# Candunio.net
KiCad netlist of a schematic drawn in Altium Designer
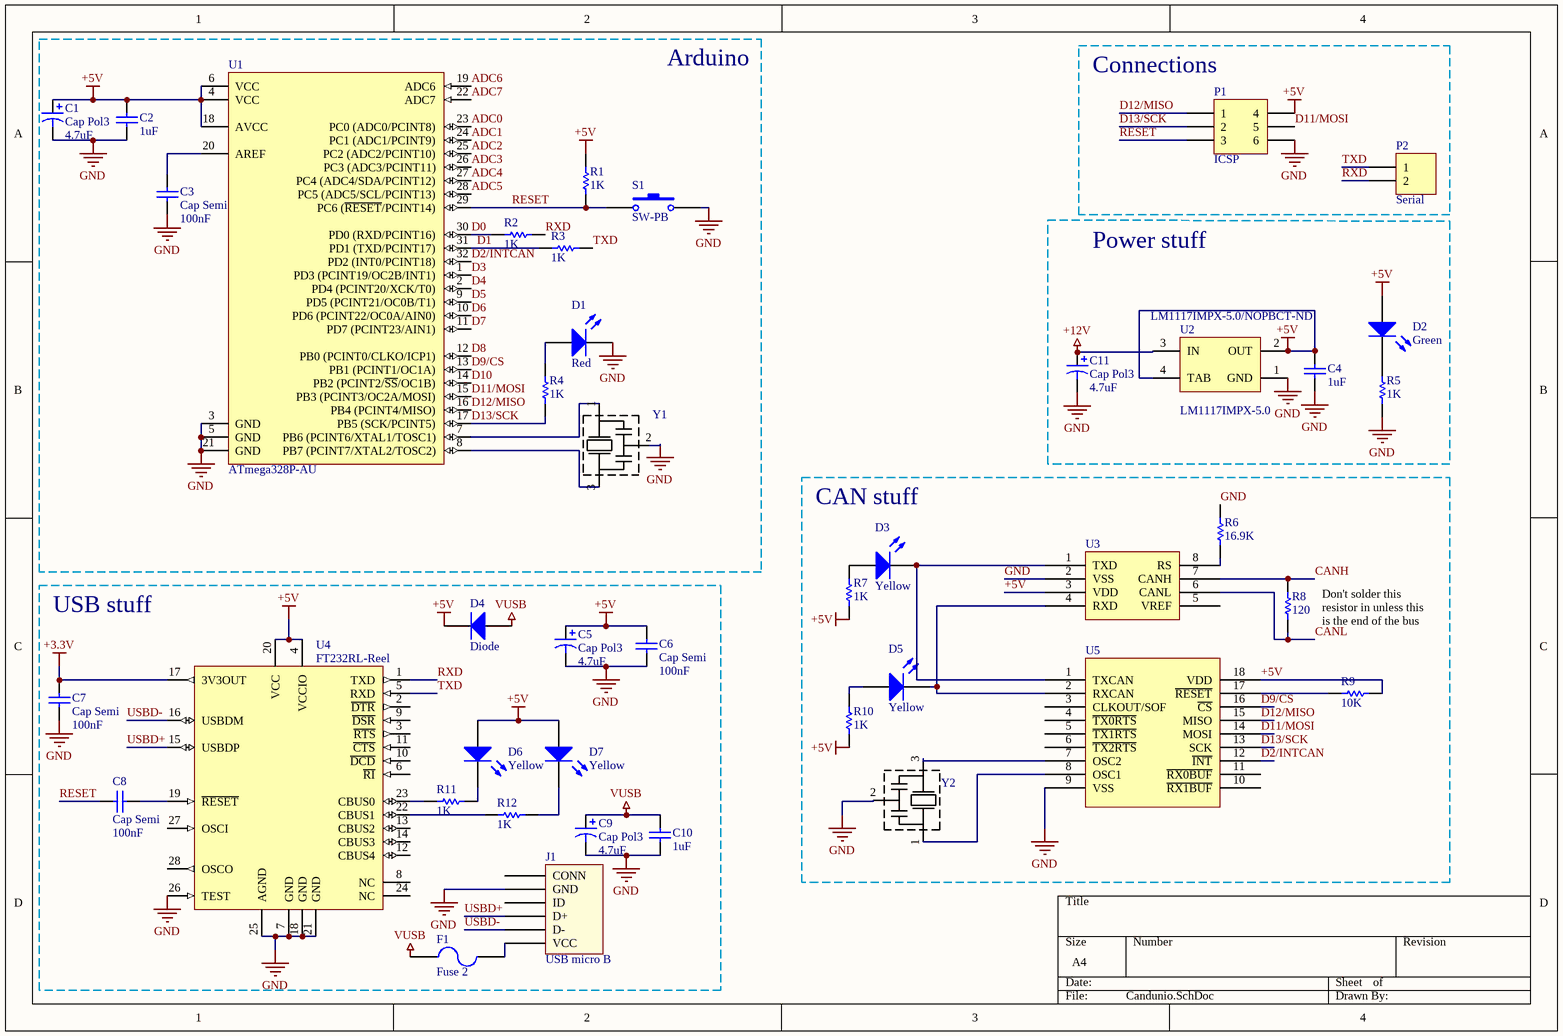
[diagram p0: Candunio.SchDoc]

(export (version "E")
  (design (tool "Eeschema 10.0.6"))
  (components
    (comp (ref "C1")
      (value "Cap Pol3")
      (footprint "C1206")
      (description "Polarized Capacitor (Surface Mount)")
      (fields
        (field (name "ALTIUM_VALUE") "4.7uF")
        (field (name "MANUFACTURER") "Kyocera AVX")
        (field (name "MANUFACTURER PART NUMBER") "12063C475KAT2A")
        (field (name "PUBLISHER") "Altium Limited")
      )
      (libsource (lib "Miscellaneous Devices") (part "Cap Pol3"))
    )
    (comp (ref "C2")
      (value "1uF")
      (footprint "C1206")
      (description "Capacitor (Semiconductor SIM Model)")
      (fields
        (field (name "MANUFACTURER") "Murata")
        (field (name "MANUFACTURER PART NUMBER") "GRM31MR71H105KA88L")
        (field (name "PUBLISHER") "Altium Limited")
      )
      (libsource (lib "Miscellaneous Devices") (part "Cap Semi"))
    )
    (comp (ref "C3")
      (value "Cap Semi")
      (footprint "C1206")
      (description "Capacitor (Semiconductor SIM Model)")
      (fields
        (field (name "ALTIUM_VALUE") "100nF")
        (field (name "MANUFACTURER") "Yageo")
        (field (name "MANUFACTURER PART NUMBER") "CC1206KKX7R0BB104")
        (field (name "PUBLISHER") "Altium Limited")
      )
      (libsource (lib "Miscellaneous Devices") (part "Cap Semi"))
    )
    (comp (ref "C4")
      (value "1uF")
      (footprint "C1206")
      (description "Capacitor (Semiconductor SIM Model)")
      (fields
        (field (name "MANUFACTURER") "Murata")
        (field (name "MANUFACTURER PART NUMBER") "GRM31MR71H105KA88L")
        (field (name "PUBLISHER") "Altium Limited")
      )
      (libsource (lib "Miscellaneous Devices") (part "Cap Semi"))
    )
    (comp (ref "C5")
      (value "Cap Pol3")
      (footprint "C1206")
      (description "Polarized Capacitor (Surface Mount)")
      (fields
        (field (name "ALTIUM_VALUE") "4.7uF")
        (field (name "MANUFACTURER") "Kyocera AVX")
        (field (name "MANUFACTURER PART NUMBER") "12063C475KAT2A")
        (field (name "PUBLISHER") "Altium Limited")
      )
      (libsource (lib "Miscellaneous Devices") (part "Cap Pol3"))
    )
    (comp (ref "C6")
      (value "Cap Semi")
      (footprint "C1206")
      (description "Capacitor (Semiconductor SIM Model)")
      (fields
        (field (name "ALTIUM_VALUE") "100nF")
        (field (name "MANUFACTURER") "Yageo")
        (field (name "MANUFACTURER PART NUMBER") "CC1206KKX7R0BB104")
        (field (name "PUBLISHER") "Altium Limited")
      )
      (libsource (lib "Miscellaneous Devices") (part "Cap Semi"))
    )
    (comp (ref "C7")
      (value "Cap Semi")
      (footprint "C1206")
      (description "Capacitor (Semiconductor SIM Model)")
      (fields
        (field (name "ALTIUM_VALUE") "100nF")
        (field (name "MANUFACTURER") "Yageo")
        (field (name "MANUFACTURER PART NUMBER") "CC1206KKX7R0BB104")
        (field (name "PUBLISHER") "Altium Limited")
      )
      (libsource (lib "Miscellaneous Devices") (part "Cap Semi"))
    )
    (comp (ref "C8")
      (value "Cap Semi")
      (footprint "C1206")
      (description "Capacitor (Semiconductor SIM Model)")
      (fields
        (field (name "ALTIUM_VALUE") "100nF")
        (field (name "MANUFACTURER") "Yageo")
        (field (name "MANUFACTURER PART NUMBER") "CC1206KKX7R0BB104")
        (field (name "PUBLISHER") "Altium Limited")
      )
      (libsource (lib "Miscellaneous Devices") (part "Cap Semi"))
    )
    (comp (ref "C9")
      (value "Cap Pol3")
      (footprint "C1206")
      (description "Polarized Capacitor (Surface Mount)")
      (fields
        (field (name "ALTIUM_VALUE") "4.7uF")
        (field (name "MANUFACTURER") "Kyocera AVX")
        (field (name "MANUFACTURER PART NUMBER") "12063C475KAT2A")
        (field (name "PUBLISHER") "Altium Limited")
      )
      (libsource (lib "Miscellaneous Devices") (part "Cap Pol3"))
    )
    (comp (ref "C10")
      (value "1uF")
      (footprint "C1206")
      (description "Capacitor (Semiconductor SIM Model)")
      (fields
        (field (name "MANUFACTURER") "Murata")
        (field (name "MANUFACTURER PART NUMBER") "GRM31MR71H105KA88L")
        (field (name "PUBLISHER") "Altium Limited")
      )
      (libsource (lib "Miscellaneous Devices") (part "Cap Semi"))
    )
    (comp (ref "C11")
      (value "Cap Pol3")
      (footprint "C1206")
      (description "Polarized Capacitor (Surface Mount)")
      (fields
        (field (name "ALTIUM_VALUE") "4.7uF")
        (field (name "MANUFACTURER") "Kyocera AVX")
        (field (name "MANUFACTURER PART NUMBER") "12063C475KAT2A")
        (field (name "PUBLISHER") "Altium Limited")
      )
      (libsource (lib "Miscellaneous Devices") (part "Cap Pol3"))
    )
    (comp (ref "D1")
      (value "Red")
      (footprint "3.2X1.6X1.1")
      (description "Typical RED, GREEN, YELLOW, AMBER GaAs LED")
      (fields
        (field (name "MANUFACTURER") "Broadcom Avago")
        (field (name "MANUFACTURER PART NUMBER") "HSMY-C150")
        (field (name "PUBLISHER") "Altium Limited")
      )
      (libsource (lib "Miscellaneous Devices") (part "LED2"))
    )
    (comp (ref "D2")
      (value "Green")
      (footprint "3.2X1.6X1.1")
      (description "Typical RED, GREEN, YELLOW, AMBER GaAs LED")
      (fields
        (field (name "MANUFACTURER") "Broadcom Avago")
        (field (name "MANUFACTURER PART NUMBER") "HSMG-C150")
        (field (name "PUBLISHER") "Altium Limited")
      )
      (libsource (lib "Miscellaneous Devices") (part "LED2"))
    )
    (comp (ref "D3")
      (value "Yellow")
      (footprint "3.2X1.6X1.1")
      (description "Typical RED, GREEN, YELLOW, AMBER GaAs LED")
      (fields
        (field (name "MANUFACTURER") "Broadcom Avago")
        (field (name "MANUFACTURER PART NUMBER") "HSMY-C150")
        (field (name "PUBLISHER") "Altium Limited")
      )
      (libsource (lib "Miscellaneous Devices") (part "LED2"))
    )
    (comp (ref "D4")
      (value "Diode")
      (footprint "SMC")
      (description "Default Diode")
      (fields (field (name "PUBLISHER") "Altium Limited"))
      (libsource (lib "Miscellaneous Devices") (part "Diode"))
    )
    (comp (ref "D5")
      (value "Yellow")
      (footprint "3.2X1.6X1.1")
      (description "Typical RED, GREEN, YELLOW, AMBER GaAs LED")
      (fields
        (field (name "MANUFACTURER") "Broadcom Avago")
        (field (name "MANUFACTURER PART NUMBER") "HSMY-C150")
        (field (name "PUBLISHER") "Altium Limited")
      )
      (libsource (lib "Miscellaneous Devices") (part "LED2"))
    )
    (comp (ref "D6")
      (value "Yellow")
      (footprint "3.2X1.6X1.1")
      (description "Typical RED, GREEN, YELLOW, AMBER GaAs LED")
      (fields
        (field (name "MANUFACTURER") "Broadcom Avago")
        (field (name "MANUFACTURER PART NUMBER") "HSMY-C150")
        (field (name "PUBLISHER") "Altium Limited")
      )
      (libsource (lib "Miscellaneous Devices") (part "LED2"))
    )
    (comp (ref "D7")
      (value "Yellow")
      (footprint "3.2X1.6X1.1")
      (description "Typical RED, GREEN, YELLOW, AMBER GaAs LED")
      (fields
        (field (name "MANUFACTURER") "Broadcom Avago")
        (field (name "MANUFACTURER PART NUMBER") "HSMY-C150")
        (field (name "PUBLISHER") "Altium Limited")
      )
      (libsource (lib "Miscellaneous Devices") (part "LED2"))
    )
    (comp (ref "F1")
      (value "Fuse 2")
      (footprint "1812")
      (description "Fuse")
      (fields
        (field (name "PART NUMBER") "MF-MSMF050-2")
        (field (name "MANUFACTURER") "Bourns")
        (field (name "PUBLISHER") "Altium Limited")
      )
      (libsource (lib "Miscellaneous Devices") (part "Fuse 2"))
    )
    (comp (ref "J1")
      (value "USB micro B")
      (footprint "1050170001")
      (description "CONN SM TH USB MICRO MODIFIED FOR DRILL")
      (fields (field (name "PART NUMBER") "WM1399CT-ND"))
      (libsource (lib "electronpowered") (part "1050170001"))
    )
    (comp (ref "P1")
      (value "ICSP")
      (footprint "HDR2X3_CEN")
      (description "Header, 3-Pin, Dual row")
      (fields (field (name "PUBLISHER") "Altium Limited"))
      (libsource (lib "Miscellaneous Connectors") (part "Header 3X2A"))
    )
    (comp (ref "P2")
      (value "Serial")
      (footprint "HDR1X2")
      (description "Header, 2-Pin")
      (fields (field (name "PUBLISHER") "Altium Limited"))
      (libsource (lib "Miscellaneous Connectors") (part "Header 2"))
    )
    (comp (ref "R1")
      (value "1K")
      (footprint "C1206")
      (description "Resistor")
      (fields
        (field (name "MANUFACTURER") "Stackpole Electronics")
        (field (name "MANUFACTURER PART NUMBER") "RNCP1206FTD1K00")
      )
      (libsource (lib "Miscellaneous Devices") (part "Res1"))
    )
    (comp (ref "R2")
      (value "1K")
      (footprint "C1206")
      (description "Resistor")
      (fields
        (field (name "MANUFACTURER") "Stackpole Electronics")
        (field (name "MANUFACTURER PART NUMBER") "RNCP1206FTD1K00")
      )
      (libsource (lib "Miscellaneous Devices") (part "Res1"))
    )
    (comp (ref "R3")
      (value "1K")
      (footprint "C1206")
      (description "Resistor")
      (fields
        (field (name "MANUFACTURER") "Stackpole Electronics")
        (field (name "MANUFACTURER PART NUMBER") "RNCP1206FTD1K00")
      )
      (libsource (lib "Miscellaneous Devices") (part "Res1"))
    )
    (comp (ref "R4")
      (value "1K")
      (footprint "C1206")
      (description "Resistor")
      (fields
        (field (name "MANUFACTURER") "Stackpole Electronics")
        (field (name "MANUFACTURER PART NUMBER") "RNCP1206FTD1K00")
      )
      (libsource (lib "Miscellaneous Devices") (part "Res1"))
    )
    (comp (ref "R5")
      (value "1K")
      (footprint "C1206")
      (description "Resistor")
      (fields
        (field (name "MANUFACTURER") "Stackpole Electronics")
        (field (name "MANUFACTURER PART NUMBER") "RNCP1206FTD1K00")
      )
      (libsource (lib "Miscellaneous Devices") (part "Res1"))
    )
    (comp (ref "R6")
      (value "16.9K")
      (footprint "C1206")
      (description "Resistor")
      (fields
        (field (name "MANUFACTURER") "TE Connectivity Holsworthy")
        (field (name "MANUFACTURER PART NUMBER") "CRGH1206F16K9")
      )
      (libsource (lib "Miscellaneous Devices") (part "Res1"))
    )
    (comp (ref "R7")
      (value "1K")
      (footprint "C1206")
      (description "Resistor")
      (fields
        (field (name "MANUFACTURER") "Stackpole Electronics")
        (field (name "MANUFACTURER PART NUMBER") "RNCP1206FTD1K00")
      )
      (libsource (lib "Miscellaneous Devices") (part "Res1"))
    )
    (comp (ref "R8")
      (value "120")
      (footprint "C1206")
      (description "Resistor")
      (fields
        (field (name "MANUFACTURER") "Vishay")
        (field (name "MANUFACTURER PART NUMBER") "CRCW1206120RFKEAHP")
      )
      (libsource (lib "Miscellaneous Devices") (part "Res1"))
    )
    (comp (ref "R9")
      (value "10K")
      (footprint "C1206")
      (description "Resistor")
      (fields
        (field (name "MANUFACTURER") "Stackpole Electronics")
        (field (name "MANUFACTURER PART NUMBER") "RNCP1206FTD10K0")
      )
      (libsource (lib "Miscellaneous Devices") (part "Res1"))
    )
    (comp (ref "R10")
      (value "1K")
      (footprint "C1206")
      (description "Resistor")
      (fields
        (field (name "MANUFACTURER") "Stackpole Electronics")
        (field (name "MANUFACTURER PART NUMBER") "RNCP1206FTD1K00")
      )
      (libsource (lib "Miscellaneous Devices") (part "Res1"))
    )
    (comp (ref "R11")
      (value "1K")
      (footprint "C1206")
      (description "Resistor")
      (fields
        (field (name "MANUFACTURER") "Stackpole Electronics")
        (field (name "MANUFACTURER PART NUMBER") "RNCP1206FTD1K00")
      )
      (libsource (lib "Miscellaneous Devices") (part "Res1"))
    )
    (comp (ref "R12")
      (value "1K")
      (footprint "C1206")
      (description "Resistor")
      (fields
        (field (name "MANUFACTURER") "Stackpole Electronics")
        (field (name "MANUFACTURER PART NUMBER") "RNCP1206FTD1K00")
      )
      (libsource (lib "Miscellaneous Devices") (part "Res1"))
    )
    (comp (ref "S1")
      (value "SW-PB")
      (footprint "C1206")
      (description "Switch")
      (fields
        (field (name "MANUFACTURER") "ITT C&K")
        (field (name "MANUFACTURER PART NUMBER") "KXT331LHS")
        (field (name "PUBLISHER") "Altium Limited")
      )
      (libsource (lib "Miscellaneous Devices") (part "SW-PB"))
    )
    (comp (ref "U1")
      (value "ATmega328P-AU")
      (footprint "32A_N")
      (fields (field (name "PUBLISHER") "Altium Limited"))
      (libsource (lib "Atmel Microcontroller 8-Bit megaAVR") (part "ATmega328P-AU"))
    )
    (comp (ref "U2")
      (value "LM1117IMPX-5.0")
      (footprint "MP04A_N")
      (description "800mA Low-Dropout Linear Regulator, 4-pin SOT-223")
      (fields
        (field (name "PARTNUMBER") "LM1117IMPX-5.0/NOPBCT-ND")
        (field (name "MANUFACTURER") "National Semiconductor")
        (field (name "SUPPLIER PART NUMBER") "LM1117IMPX-5.0/NOPBCT-ND")
        (field (name "PUBLISHER") "Altium Limited")
      )
      (libsource (lib "NSC LDO") (part "LM1117IMPX-5.0"))
    )
    (comp (ref "U3")
      (value "MCP2551-E/SN")
      (footprint "SOIC127P600X175-8M")
      (description "SOIC")
      (libsource (lib "AMSComponents") (part "MCP2551-E/SN"))
    )
    (comp (ref "U4")
      (value "FT232RL-Reel")
      (footprint "SSOP-28_N")
      (description "USB UART Asynchronous Serial Data Transfer Chip, SSOP-28, Tape and Reel")
      (fields
        (field (name "MANUFACTURER") "FTDI")
        (field (name "MANUFACTURER PART NUMBER") "FT232RL-REEL")
        (field (name "PUBLISHER") "Altium Limited")
      )
      (libsource (lib "FTDI Communication UART") (part "FT232RL-Reel"))
    )
    (comp (ref "U5")
      (value "MCP2515-E/ST")
      (footprint "SOIC127P1030X265-18M")
      (description "SOIC")
      (libsource (lib "AMSComponents") (part "MCP2515-E/ST"))
    )
    (comp (ref "Y1")
      (value "CSTCE16M0V53-R0")
      (footprint "CSTCE16M0V53-R0")
      (fields
        (field (name "MANUFACTURER") "Murata")
        (field (name "MANUFACTURER PART NUMBER") "CSTCE16M0V53C-R0")
        (field (name "TOLERANCE") "0.5%")
      )
      (libsource (lib "AMSComponents") (part "CSTCE16M0V53-R0"))
    )
    (comp (ref "Y2")
      (value "CSTCE16M0V53-R0")
      (footprint "CSTCE16M0V53-R0")
      (fields
        (field (name "MANUFACTURER") "Murata")
        (field (name "MANUFACTURER PART NUMBER") "CSTCE16M0V53C-R0")
        (field (name "TOLERANCE") "0.5%")
      )
      (libsource (lib "AMSComponents") (part "CSTCE16M0V53-R0"))
    )
  )
  (nets
    (net (code "1") (name "+3.3V") (class "Default")
      (node (ref "C7") (pin "1") (pinfunction "1_1") (pintype "passive"))
      (node (ref "U4") (pin "17") (pinfunction "3V3OUT_17") (pintype "output"))
    )
    (net (code "2") (name "+5V") (class "Default")
      (node (ref "C1") (pin "1") (pinfunction "1_1") (pintype "passive"))
      (node (ref "C2") (pin "1") (pinfunction "1_1") (pintype "passive"))
      (node (ref "C4") (pin "1") (pinfunction "1_1") (pintype "passive"))
      (node (ref "C5") (pin "1") (pinfunction "1_1") (pintype "passive"))
      (node (ref "C6") (pin "1") (pinfunction "1_1") (pintype "passive"))
      (node (ref "D2") (pin "1") (pinfunction "A_1") (pintype "passive"))
      (node (ref "D4") (pin "2") (pinfunction "K_2") (pintype "passive"))
      (node (ref "D6") (pin "1") (pinfunction "A_1") (pintype "passive"))
      (node (ref "D7") (pin "1") (pinfunction "A_1") (pintype "passive"))
      (node (ref "P1") (pin "4") (pinfunction "4_4") (pintype "passive"))
      (node (ref "R1") (pin "1") (pinfunction "1_1") (pintype "passive"))
      (node (ref "R10") (pin "2") (pinfunction "2_2") (pintype "passive"))
      (node (ref "R7") (pin "1") (pinfunction "1_1") (pintype "passive"))
      (node (ref "R9") (pin "2") (pinfunction "2_2") (pintype "passive"))
      (node (ref "U1") (pin "18") (pinfunction "AVCC_18") (pintype "power_in"))
      (node (ref "U1") (pin "4") (pinfunction "VCC_4") (pintype "power_in"))
      (node (ref "U1") (pin "6") (pinfunction "VCC_6") (pintype "power_in"))
      (node (ref "U2") (pin "2") (pinfunction "OUT_2") (pintype "power_in"))
      (node (ref "U2") (pin "4") (pinfunction "TAB_4") (pintype "power_in"))
      (node (ref "U3") (pin "3") (pinfunction "VDD_3") (pintype "passive"))
      (node (ref "U4") (pin "20") (pinfunction "VCC_20") (pintype "power_in"))
      (node (ref "U4") (pin "4") (pinfunction "VCCIO_4") (pintype "power_in"))
      (node (ref "U5") (pin "18") (pinfunction "VDD_18") (pintype "passive"))
    )
    (net (code "3") (name "+12V") (class "Default")
      (node (ref "C11") (pin "1") (pinfunction "1_1") (pintype "passive"))
      (node (ref "U2") (pin "3") (pinfunction "IN_3") (pintype "power_in"))
    )
    (net (code "4") (name "/ADC0") (class "Default")
      (node (ref "U1") (pin "23") (pinfunction "PC0_(ADC0/PCINT8)_23") (pintype "bidirectional"))
    )
    (net (code "5") (name "/ADC1") (class "Default")
      (node (ref "U1") (pin "24") (pinfunction "PC1_(ADC1/PCINT9)_24") (pintype "bidirectional"))
    )
    (net (code "6") (name "/ADC2") (class "Default")
      (node (ref "U1") (pin "25") (pinfunction "PC2_(ADC2/PCINT10)_25") (pintype "bidirectional"))
    )
    (net (code "7") (name "/ADC3") (class "Default")
      (node (ref "U1") (pin "26") (pinfunction "PC3_(ADC3/PCINT11)_26") (pintype "bidirectional"))
    )
    (net (code "8") (name "/ADC4") (class "Default")
      (node (ref "U1") (pin "27") (pinfunction "PC4_(ADC4/SDA/PCINT12)_27") (pintype "bidirectional"))
    )
    (net (code "9") (name "/ADC5") (class "Default")
      (node (ref "U1") (pin "28") (pinfunction "PC5_(ADC5/SCL/PCINT13)_28") (pintype "bidirectional"))
    )
    (net (code "10") (name "/ADC6") (class "Default")
      (node (ref "U1") (pin "19") (pinfunction "ADC6_19") (pintype "input"))
    )
    (net (code "11") (name "/ADC7") (class "Default")
      (node (ref "U1") (pin "22") (pinfunction "ADC7_22") (pintype "input"))
    )
    (net (code "12") (name "/CANH") (class "Default")
      (node (ref "R8") (pin "1") (pinfunction "1_1") (pintype "passive"))
      (node (ref "U3") (pin "7") (pinfunction "CANH_7") (pintype "passive"))
    )
    (net (code "13") (name "/CANL") (class "Default")
      (node (ref "R8") (pin "2") (pinfunction "2_2") (pintype "passive"))
      (node (ref "U3") (pin "6") (pinfunction "CANL_6") (pintype "passive"))
    )
    (net (code "14") (name "/D0") (class "Default")
      (node (ref "R2") (pin "1") (pinfunction "1_1") (pintype "passive"))
      (node (ref "U1") (pin "30") (pinfunction "PD0_(RXD/PCINT16)_30") (pintype "bidirectional"))
    )
    (net (code "15") (name "/D1") (class "Default")
      (node (ref "R3") (pin "1") (pinfunction "1_1") (pintype "passive"))
      (node (ref "U1") (pin "31") (pinfunction "PD1_(TXD/PCINT17)_31") (pintype "bidirectional"))
    )
    (net (code "16") (name "/D2{slash}INTCAN") (class "Default")
      (node (ref "U1") (pin "32") (pinfunction "PD2_(INT0/PCINT18)_32") (pintype "bidirectional"))
      (node (ref "U5") (pin "12") (pinfunction "~{INT}_12") (pintype "passive"))
    )
    (net (code "17") (name "/D3") (class "Default")
      (node (ref "U1") (pin "1") (pinfunction "PD3_(PCINT19/OC2B/INT1)_1") (pintype "bidirectional"))
    )
    (net (code "18") (name "/D4") (class "Default")
      (node (ref "U1") (pin "2") (pinfunction "PD4_(PCINT20/XCK/T0)_2") (pintype "bidirectional"))
    )
    (net (code "19") (name "/D5") (class "Default")
      (node (ref "U1") (pin "9") (pinfunction "PD5_(PCINT21/OC0B/T1)_9") (pintype "bidirectional"))
    )
    (net (code "20") (name "/D6") (class "Default")
      (node (ref "U1") (pin "10") (pinfunction "PD6_(PCINT22/OC0A/AIN0)_10") (pintype "bidirectional"))
    )
    (net (code "21") (name "/D7") (class "Default")
      (node (ref "U1") (pin "11") (pinfunction "PD7_(PCINT23/AIN1)_11") (pintype "bidirectional"))
    )
    (net (code "22") (name "/D8") (class "Default")
      (node (ref "U1") (pin "12") (pinfunction "PB0_(PCINT0/CLKO/ICP1)_12") (pintype "bidirectional"))
    )
    (net (code "23") (name "/D9{slash}CS") (class "Default")
      (node (ref "U1") (pin "13") (pinfunction "PB1_(PCINT1/OC1A)_13") (pintype "bidirectional"))
      (node (ref "U5") (pin "16") (pinfunction "~{CS}_16") (pintype "passive"))
    )
    (net (code "24") (name "/D10") (class "Default")
      (node (ref "U1") (pin "14") (pinfunction "PB2_(PCINT2/~{SS}/OC1B)_14") (pintype "bidirectional"))
    )
    (net (code "25") (name "/D11{slash}MOSI") (class "Default")
      (node (ref "P1") (pin "5") (pinfunction "5_5") (pintype "passive"))
      (node (ref "U1") (pin "15") (pinfunction "PB3_(PCINT3/OC2A/MOSI)_15") (pintype "bidirectional"))
      (node (ref "U5") (pin "14") (pinfunction "MOSI_14") (pintype "passive"))
    )
    (net (code "26") (name "/D12{slash}MISO") (class "Default")
      (node (ref "P1") (pin "1") (pinfunction "1_1") (pintype "passive"))
      (node (ref "U1") (pin "16") (pinfunction "PB4_(PCINT4/MISO)_16") (pintype "bidirectional"))
      (node (ref "U5") (pin "15") (pinfunction "MISO_15") (pintype "passive"))
    )
    (net (code "27") (name "/D13{slash}SCK") (class "Default")
      (node (ref "P1") (pin "2") (pinfunction "2_2") (pintype "passive"))
      (node (ref "R4") (pin "2") (pinfunction "2_2") (pintype "passive"))
      (node (ref "U1") (pin "17") (pinfunction "PB5_(SCK/PCINT5)_17") (pintype "bidirectional"))
      (node (ref "U5") (pin "13") (pinfunction "SCK_13") (pintype "passive"))
    )
    (net (code "28") (name "/RESET") (class "Default")
      (node (ref "C8") (pin "1") (pinfunction "1_1") (pintype "passive"))
      (node (ref "P1") (pin "3") (pinfunction "3_3") (pintype "passive"))
      (node (ref "R1") (pin "2") (pinfunction "2_2") (pintype "passive"))
      (node (ref "S1") (pin "1") (pinfunction "1_1") (pintype "passive"))
      (node (ref "U1") (pin "29") (pinfunction "PC6_(~{RESET}/PCINT14)_29") (pintype "bidirectional"))
    )
    (net (code "29") (name "/RXD") (class "Default")
      (node (ref "P2") (pin "2") (pinfunction "2_2") (pintype "passive"))
      (node (ref "R2") (pin "2") (pinfunction "2_2") (pintype "passive"))
      (node (ref "U4") (pin "1") (pinfunction "TXD_1") (pintype "output"))
    )
    (net (code "30") (name "/TXD") (class "Default")
      (node (ref "P2") (pin "1") (pinfunction "1_1") (pintype "passive"))
      (node (ref "R3") (pin "2") (pinfunction "2_2") (pintype "passive"))
      (node (ref "U4") (pin "5") (pinfunction "RXD_5") (pintype "input"))
    )
    (net (code "31") (name "/USBD+") (class "Default")
      (node (ref "J1") (pin "3") (pinfunction "D+_3") (pintype "passive"))
      (node (ref "U4") (pin "15") (pinfunction "USBDP_15") (pintype "bidirectional"))
    )
    (net (code "32") (name "/USBD-") (class "Default")
      (node (ref "J1") (pin "2") (pinfunction "D-_2") (pintype "passive"))
      (node (ref "U4") (pin "16") (pinfunction "USBDM_16") (pintype "bidirectional"))
    )
    (net (code "33") (name "GND") (class "Default")
      (node (ref "C1") (pin "2") (pinfunction "2_2") (pintype "passive"))
      (node (ref "C10") (pin "2") (pinfunction "2_2") (pintype "passive"))
      (node (ref "C11") (pin "2") (pinfunction "2_2") (pintype "passive"))
      (node (ref "C2") (pin "2") (pinfunction "2_2") (pintype "passive"))
      (node (ref "C3") (pin "2") (pinfunction "2_2") (pintype "passive"))
      (node (ref "C4") (pin "2") (pinfunction "2_2") (pintype "passive"))
      (node (ref "C5") (pin "2") (pinfunction "2_2") (pintype "passive"))
      (node (ref "C6") (pin "2") (pinfunction "2_2") (pintype "passive"))
      (node (ref "C7") (pin "2") (pinfunction "2_2") (pintype "passive"))
      (node (ref "C9") (pin "2") (pinfunction "2_2") (pintype "passive"))
      (node (ref "D1") (pin "2") (pinfunction "K_2") (pintype "passive"))
      (node (ref "J1") (pin "5") (pinfunction "GND_5") (pintype "passive"))
      (node (ref "P1") (pin "6") (pinfunction "6_6") (pintype "passive"))
      (node (ref "R5") (pin "2") (pinfunction "2_2") (pintype "passive"))
      (node (ref "R6") (pin "1") (pinfunction "1_1") (pintype "passive"))
      (node (ref "S1") (pin "2") (pinfunction "2_2") (pintype "passive"))
      (node (ref "U1") (pin "21") (pinfunction "GND_21") (pintype "power_in"))
      (node (ref "U1") (pin "3") (pinfunction "GND_3") (pintype "power_in"))
      (node (ref "U1") (pin "5") (pinfunction "GND_5") (pintype "power_in"))
      (node (ref "U2") (pin "1") (pinfunction "GND_1") (pintype "power_in"))
      (node (ref "U3") (pin "2") (pinfunction "VSS_2") (pintype "passive"))
      (node (ref "U4") (pin "18") (pinfunction "GND_18") (pintype "power_in"))
      (node (ref "U4") (pin "21") (pinfunction "GND_21") (pintype "power_in"))
      (node (ref "U4") (pin "25") (pinfunction "AGND_25") (pintype "power_in"))
      (node (ref "U4") (pin "26") (pinfunction "TEST_26") (pintype "input"))
      (node (ref "U4") (pin "7") (pinfunction "GND_7") (pintype "power_in"))
      (node (ref "U5") (pin "9") (pinfunction "VSS_9") (pintype "passive"))
      (node (ref "Y1") (pin "2") (pinfunction "2_2") (pintype "passive"))
      (node (ref "Y2") (pin "2") (pinfunction "2_2") (pintype "passive"))
    )
    (net (code "34") (name "Net-(D1-A)") (class "Default")
      (node (ref "D1") (pin "1") (pinfunction "A_1") (pintype "passive"))
      (node (ref "R4") (pin "1") (pinfunction "1_1") (pintype "passive"))
    )
    (net (code "35") (name "Net-(D2-K)") (class "Default")
      (node (ref "D2") (pin "2") (pinfunction "K_2") (pintype "passive"))
      (node (ref "R5") (pin "1") (pinfunction "1_1") (pintype "passive"))
    )
    (net (code "36") (name "Net-(D3-A)") (class "Default")
      (node (ref "D3") (pin "1") (pinfunction "A_1") (pintype "passive"))
      (node (ref "R7") (pin "2") (pinfunction "2_2") (pintype "passive"))
    )
    (net (code "37") (name "Net-(D3-K)") (class "Default")
      (node (ref "D3") (pin "2") (pinfunction "K_2") (pintype "passive"))
      (node (ref "U3") (pin "1") (pinfunction "TXD_1") (pintype "passive"))
      (node (ref "U5") (pin "1") (pinfunction "TXCAN_1") (pintype "passive"))
    )
    (net (code "38") (name "Net-(D5-A)") (class "Default")
      (node (ref "D5") (pin "1") (pinfunction "A_1") (pintype "passive"))
      (node (ref "R10") (pin "1") (pinfunction "1_1") (pintype "passive"))
    )
    (net (code "39") (name "Net-(D5-K)") (class "Default")
      (node (ref "D5") (pin "2") (pinfunction "K_2") (pintype "passive"))
      (node (ref "U3") (pin "4") (pinfunction "RXD_4") (pintype "passive"))
      (node (ref "U5") (pin "2") (pinfunction "RXCAN_2") (pintype "passive"))
    )
    (net (code "40") (name "Net-(D6-K)") (class "Default")
      (node (ref "D6") (pin "2") (pinfunction "K_2") (pintype "passive"))
      (node (ref "R11") (pin "2") (pinfunction "2_2") (pintype "passive"))
    )
    (net (code "41") (name "Net-(D7-K)") (class "Default")
      (node (ref "D7") (pin "2") (pinfunction "K_2") (pintype "passive"))
      (node (ref "R12") (pin "2") (pinfunction "2_2") (pintype "passive"))
    )
    (net (code "42") (name "Net-(J1-VCC)") (class "Default")
      (node (ref "F1") (pin "2") (pinfunction "2_2") (pintype "passive"))
      (node (ref "J1") (pin "1") (pinfunction "VCC_1") (pintype "passive"))
    )
    (net (code "43") (name "Net-(U1-AREF)") (class "Default")
      (node (ref "C3") (pin "1") (pinfunction "1_1") (pintype "passive"))
      (node (ref "U1") (pin "20") (pinfunction "AREF_20") (pintype "passive"))
    )
    (net (code "44") (name "Net-(U1-PB6_(PCINT6{slash}XTAL1{slash}TOSC1))") (class "Default")
      (node (ref "U1") (pin "7") (pinfunction "PB6_(PCINT6/XTAL1/TOSC1)_7") (pintype "bidirectional"))
      (node (ref "Y1") (pin "1") (pinfunction "1_1") (pintype "passive"))
    )
    (net (code "45") (name "Net-(U1-PB7_(PCINT7{slash}XTAL2{slash}TOSC2))") (class "Default")
      (node (ref "U1") (pin "8") (pinfunction "PB7_(PCINT7/XTAL2/TOSC2)_8") (pintype "bidirectional"))
      (node (ref "Y1") (pin "3") (pinfunction "3_3") (pintype "passive"))
    )
    (net (code "46") (name "Net-(U3-RS)") (class "Default")
      (node (ref "R6") (pin "2") (pinfunction "2_2") (pintype "passive"))
      (node (ref "U3") (pin "8") (pinfunction "RS_8") (pintype "passive"))
    )
    (net (code "47") (name "Net-(U4-CBUS0)") (class "Default")
      (node (ref "R11") (pin "1") (pinfunction "1_1") (pintype "passive"))
      (node (ref "U4") (pin "23") (pinfunction "CBUS0_23") (pintype "bidirectional"))
    )
    (net (code "48") (name "Net-(U4-CBUS1)") (class "Default")
      (node (ref "R12") (pin "1") (pinfunction "1_1") (pintype "passive"))
      (node (ref "U4") (pin "22") (pinfunction "CBUS1_22") (pintype "bidirectional"))
    )
    (net (code "49") (name "Net-(U4-~{RESET})") (class "Default")
      (node (ref "C8") (pin "2") (pinfunction "2_2") (pintype "passive"))
      (node (ref "U4") (pin "19") (pinfunction "~{RESET}_19") (pintype "input"))
    )
    (net (code "50") (name "Net-(U5-OSC1)") (class "Default")
      (node (ref "U5") (pin "8") (pinfunction "OSC1_8") (pintype "passive"))
      (node (ref "Y2") (pin "1") (pinfunction "1_1") (pintype "passive"))
    )
    (net (code "51") (name "Net-(U5-OSC2)") (class "Default")
      (node (ref "U5") (pin "7") (pinfunction "OSC2_7") (pintype "passive"))
      (node (ref "Y2") (pin "3") (pinfunction "3_3") (pintype "passive"))
    )
    (net (code "52") (name "Net-(U5-~{RESET})") (class "Default")
      (node (ref "R9") (pin "1") (pinfunction "1_1") (pintype "passive"))
      (node (ref "U5") (pin "17") (pinfunction "~{RESET}_17") (pintype "passive"))
    )
    (net (code "53") (name "VUSB") (class "Default")
      (node (ref "C10") (pin "1") (pinfunction "1_1") (pintype "passive"))
      (node (ref "C9") (pin "1") (pinfunction "1_1") (pintype "passive"))
      (node (ref "D4") (pin "1") (pinfunction "A_1") (pintype "passive"))
      (node (ref "F1") (pin "1") (pinfunction "1_1") (pintype "passive"))
    )
    (net (code "54") (name "unconnected-(J1-CONN-Pad0)") (class "Default")
      (node (ref "J1") (pin "0") (pinfunction "CONN_0") (pintype "passive"))
    )
    (net (code "55") (name "unconnected-(J1-ID-Pad4)") (class "Default")
      (node (ref "J1") (pin "4") (pinfunction "ID_4") (pintype "passive"))
    )
    (net (code "56") (name "unconnected-(U3-VREF-Pad5)") (class "Default")
      (node (ref "U3") (pin "5") (pinfunction "VREF_5") (pintype "passive"))
    )
    (net (code "57") (name "unconnected-(U4-CBUS2-Pad13)") (class "Default")
      (node (ref "U4") (pin "13") (pinfunction "CBUS2_13") (pintype "bidirectional"))
    )
    (net (code "58") (name "unconnected-(U4-CBUS3-Pad14)") (class "Default")
      (node (ref "U4") (pin "14") (pinfunction "CBUS3_14") (pintype "bidirectional"))
    )
    (net (code "59") (name "unconnected-(U4-CBUS4-Pad12)") (class "Default")
      (node (ref "U4") (pin "12") (pinfunction "CBUS4_12") (pintype "bidirectional"))
    )
    (net (code "60") (name "unconnected-(U4-NC-Pad8)") (class "Default")
      (node (ref "U4") (pin "8") (pinfunction "NC_8") (pintype "passive"))
    )
    (net (code "61") (name "unconnected-(U4-NC-Pad24)") (class "Default")
      (node (ref "U4") (pin "24") (pinfunction "NC_24") (pintype "passive"))
    )
    (net (code "62") (name "unconnected-(U4-OSCI-Pad27)") (class "Default")
      (node (ref "U4") (pin "27") (pinfunction "OSCI_27") (pintype "input"))
    )
    (net (code "63") (name "unconnected-(U4-OSCO-Pad28)") (class "Default")
      (node (ref "U4") (pin "28") (pinfunction "OSCO_28") (pintype "output"))
    )
    (net (code "64") (name "unconnected-(U4-~{CTS}-Pad11)") (class "Default")
      (node (ref "U4") (pin "11") (pinfunction "~{CTS}_11") (pintype "input"))
    )
    (net (code "65") (name "unconnected-(U4-~{DCD}-Pad10)") (class "Default")
      (node (ref "U4") (pin "10") (pinfunction "~{DCD}_10") (pintype "input"))
    )
    (net (code "66") (name "unconnected-(U4-~{DSR}-Pad9)") (class "Default")
      (node (ref "U4") (pin "9") (pinfunction "~{DSR}_9") (pintype "input"))
    )
    (net (code "67") (name "unconnected-(U4-~{DTR}-Pad2)") (class "Default")
      (node (ref "U4") (pin "2") (pinfunction "~{DTR}_2") (pintype "output"))
    )
    (net (code "68") (name "unconnected-(U4-~{RI}-Pad6)") (class "Default")
      (node (ref "U4") (pin "6") (pinfunction "~{RI}_6") (pintype "input"))
    )
    (net (code "69") (name "unconnected-(U4-~{RTS}-Pad3)") (class "Default")
      (node (ref "U4") (pin "3") (pinfunction "~{RTS}_3") (pintype "output"))
    )
    (net (code "70") (name "unconnected-(U5-CLKOUT{slash}SOF-Pad3)") (class "Default")
      (node (ref "U5") (pin "3") (pinfunction "CLKOUT/SOF_3") (pintype "passive"))
    )
    (net (code "71") (name "unconnected-(U5-~{RX0BUF}-Pad11)") (class "Default")
      (node (ref "U5") (pin "11") (pinfunction "~{RX0BUF}_11") (pintype "passive"))
    )
    (net (code "72") (name "unconnected-(U5-~{RX1BUF}-Pad10)") (class "Default")
      (node (ref "U5") (pin "10") (pinfunction "~{RX1BUF}_10") (pintype "passive"))
    )
    (net (code "73") (name "unconnected-(U5-~{TX0RTS}-Pad4)") (class "Default")
      (node (ref "U5") (pin "4") (pinfunction "~{TX0RTS}_4") (pintype "passive"))
    )
    (net (code "74") (name "unconnected-(U5-~{TX1RTS}-Pad5)") (class "Default")
      (node (ref "U5") (pin "5") (pinfunction "~{TX1RTS}_5") (pintype "passive"))
    )
    (net (code "75") (name "unconnected-(U5-~{TX2RTS}-Pad6)") (class "Default")
      (node (ref "U5") (pin "6") (pinfunction "~{TX2RTS}_6") (pintype "passive"))
    )
  )
)
